# warship_demo_1.net
KiCad netlist of a schematic drawn in Altium Designer
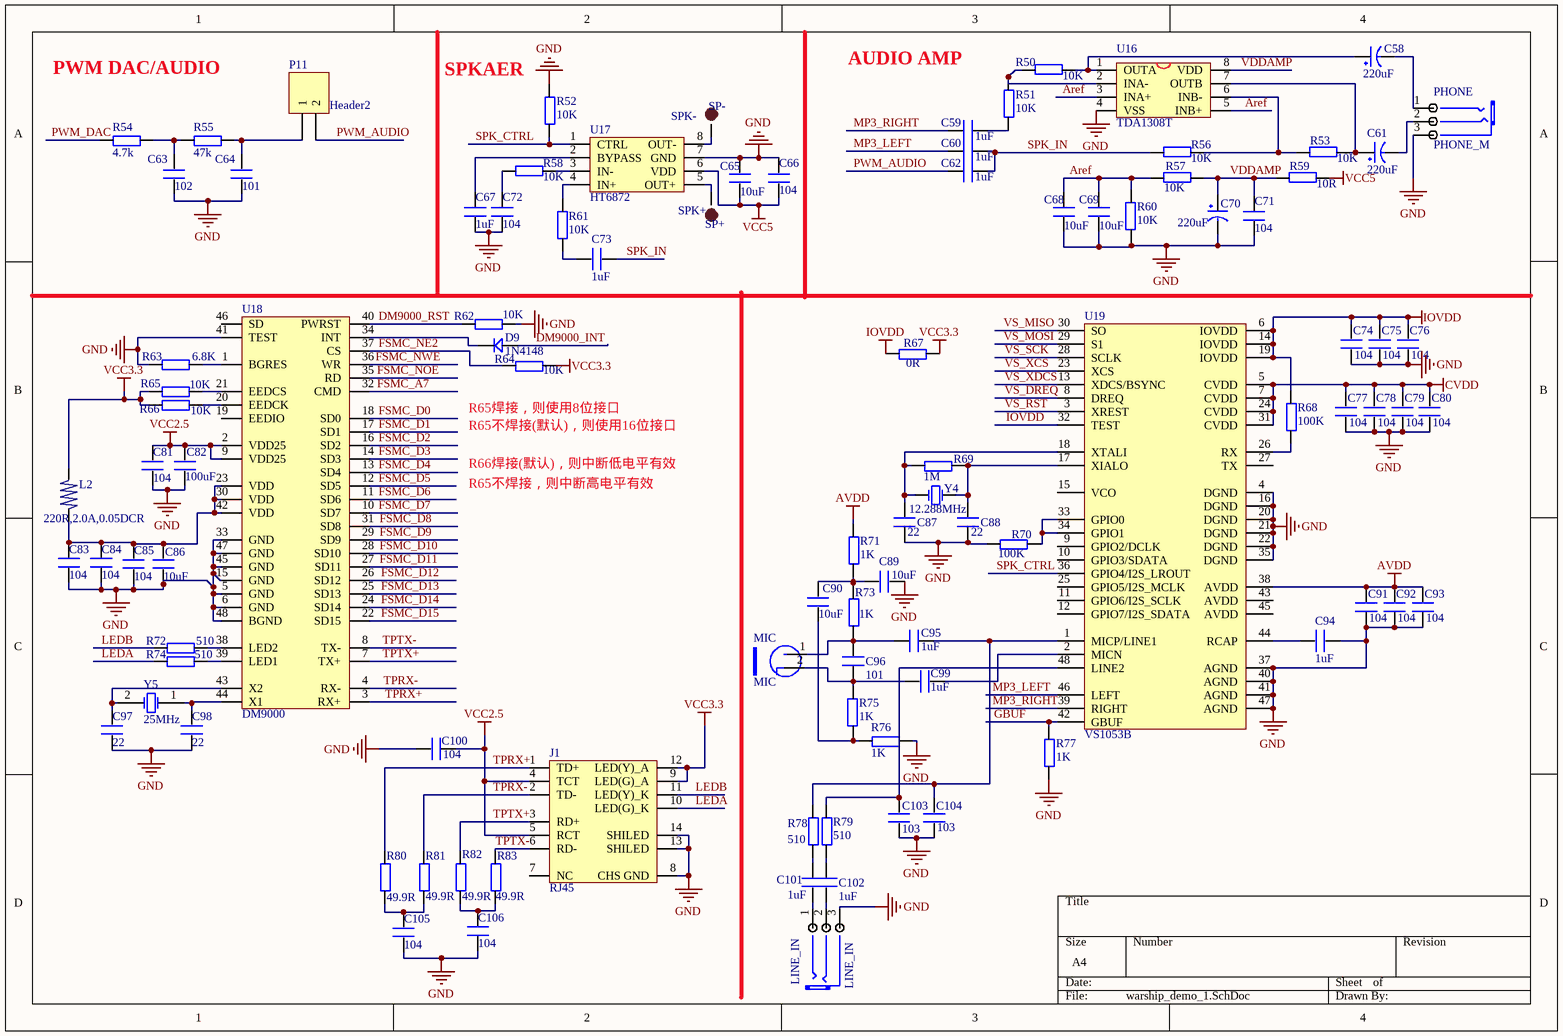
[diagram p0: warship_demo_1.SchDoc]

(export (version "E")
  (design (tool "Eeschema 10.0.6"))
  (components
    (comp (ref "C58") (value "220uF") (footprint "CC6.56.5") (libsource (lib "") (part "CAP_1")))
    (comp (ref "C59") (value "1uF") (footprint "0603P") (libsource (lib "WarShip V3 STM32103封装库") (part "C")))
    (comp (ref "C60") (value "1uF") (footprint "0603P") (libsource (lib "WarShip V3 STM32103封装库") (part "C")))
    (comp (ref "C61") (value "220uF") (footprint "CC6.56.5") (libsource (lib "") (part "CAP_1")))
    (comp (ref "C62") (value "1uF") (footprint "0603P") (libsource (lib "WarShip V3 STM32103封装库") (part "C")))
    (comp (ref "C63") (value "102") (footprint "0603P") (libsource (lib "WarShip V3 STM32103封装库") (part "C")))
    (comp (ref "C64") (value "101") (footprint "0603P") (libsource (lib "WarShip V3 STM32103封装库") (part "C")))
    (comp (ref "C65") (value "10uF") (footprint "0805") (libsource (lib "WarShip V3 STM32103封装库") (part "C")))
    (comp (ref "C66") (value "104") (footprint "0603P") (libsource (lib "WarShip V3 STM32103封装库") (part "C")))
    (comp (ref "C67") (value "1uF") (footprint "0603P") (libsource (lib "WarShip V3 STM32103封装库") (part "C")))
    (comp (ref "C68") (value "10uF") (footprint "0805") (libsource (lib "WarShip V3 STM32103封装库") (part "C")))
    (comp (ref "C69") (value "10uF") (footprint "0805") (libsource (lib "WarShip V3 STM32103封装库") (part "C")))
    (comp (ref "C70")
      (value "220uF")
      (footprint "CC6.56.5")
      (libsource (lib "WarShip V3 STM32103封装库") (part "CAP"))
    )
    (comp (ref "C71") (value "104") (footprint "0603P") (libsource (lib "WarShip V3 STM32103封装库") (part "C")))
    (comp (ref "C72") (value "104") (footprint "0603P") (libsource (lib "WarShip V3 STM32103封装库") (part "C")))
    (comp (ref "C73") (value "1uF") (footprint "0603P") (libsource (lib "WarShip V3 STM32103封装库") (part "C")))
    (comp (ref "C74") (value "104") (footprint "0603P") (libsource (lib "MP3模块封装库") (part "C")))
    (comp (ref "C75") (value "104") (footprint "0603P") (libsource (lib "MP3模块封装库") (part "C")))
    (comp (ref "C76") (value "104") (footprint "0603P") (libsource (lib "MP3模块封装库") (part "C")))
    (comp (ref "C77") (value "104") (footprint "0603P") (libsource (lib "MP3模块封装库") (part "C")))
    (comp (ref "C78") (value "104") (footprint "0603P") (libsource (lib "MP3模块封装库") (part "C")))
    (comp (ref "C79") (value "104") (footprint "0603P") (libsource (lib "MP3模块封装库") (part "C")))
    (comp (ref "C80") (value "104") (footprint "0603P") (libsource (lib "MP3模块封装库") (part "C")))
    (comp (ref "C81") (value "104") (footprint "0603P") (libsource (lib "WarShip V3 STM32103封装库") (part "C")))
    (comp (ref "C82")
      (value "100uF")
      (footprint "1206")
      (libsource (lib "WarShip V3 STM32103封装库") (part "C"))
    )
    (comp (ref "C83") (value "104") (footprint "0603P") (libsource (lib "WarShip V3 STM32103封装库") (part "C")))
    (comp (ref "C84") (value "104") (footprint "0603P") (libsource (lib "WarShip V3 STM32103封装库") (part "C")))
    (comp (ref "C85") (value "104") (footprint "0603P") (libsource (lib "WarShip V3 STM32103封装库") (part "C")))
    (comp (ref "C86") (value "10uF") (footprint "0805") (libsource (lib "WarShip V3 STM32103封装库") (part "C")))
    (comp (ref "C87") (value "22") (footprint "0603P") (libsource (lib "MP3模块封装库") (part "C")))
    (comp (ref "C88") (value "22") (footprint "0603P") (libsource (lib "MP3模块封装库") (part "C")))
    (comp (ref "C89") (value "10uF") (footprint "0805") (libsource (lib "WarShip V3 STM32103封装库") (part "C")))
    (comp (ref "C90") (value "10uF") (footprint "0805") (libsource (lib "WarShip V3 STM32103封装库") (part "C")))
    (comp (ref "C91") (value "104") (footprint "0603P") (libsource (lib "MP3模块封装库") (part "C")))
    (comp (ref "C92") (value "104") (footprint "0603P") (libsource (lib "MP3模块封装库") (part "C")))
    (comp (ref "C93") (value "104") (footprint "0603P") (libsource (lib "MP3模块封装库") (part "C")))
    (comp (ref "C94") (value "1uF") (footprint "0603P") (libsource (lib "MP3模块封装库") (part "C")))
    (comp (ref "C95") (value "1uF") (footprint "0603P") (libsource (lib "MP3模块封装库") (part "C")))
    (comp (ref "C96") (value "101") (footprint "0603P") (libsource (lib "MP3模块封装库") (part "C")))
    (comp (ref "C97") (value "22") (footprint "0603P") (libsource (lib "WarShip V3 STM32103封装库") (part "C")))
    (comp (ref "C98") (value "22") (footprint "0603P") (libsource (lib "WarShip V3 STM32103封装库") (part "C")))
    (comp (ref "C99") (value "1uF") (footprint "0603P") (libsource (lib "MP3模块封装库") (part "C")))
    (comp (ref "C100")
      (value "104")
      (footprint "0603P")
      (libsource (lib "WarShip V3 STM32103封装库") (part "C"))
    )
    (comp (ref "C101") (value "1uF") (footprint "0603P") (libsource (lib "MP3模块封装库") (part "C")))
    (comp (ref "C102") (value "1uF") (footprint "0603P") (libsource (lib "MP3模块封装库") (part "C")))
    (comp (ref "C103") (value "103") (footprint "0603P") (libsource (lib "MP3模块封装库") (part "C")))
    (comp (ref "C104") (value "103") (footprint "0603P") (libsource (lib "MP3模块封装库") (part "C")))
    (comp (ref "C105")
      (value "104")
      (footprint "0603P")
      (libsource (lib "WarShip V3 STM32103封装库") (part "C"))
    )
    (comp (ref "C106")
      (value "104")
      (footprint "0603P")
      (libsource (lib "WarShip V3 STM32103封装库") (part "C"))
    )
    (comp (ref "D9")
      (value "1N4148")
      (footprint "DIODE_SOP")
      (libsource (lib "WarShip V3 STM32103封装库") (part "D"))
    )
    (comp (ref "J1")
      (value "RJ45")
      (footprint "HR911105A")
      (libsource (lib "WarShip V3 STM32103封装库") (part "HR911105"))
    )
    (comp (ref "L2")
      (value "220R,2.0A,0.05DCR")
      (footprint "0603P")
      (libsource (lib "WarShip V3 STM32103封装库") (part "L"))
    )
    (comp (ref "LINE_IN")
      (value "LINE_IN")
      (footprint "PHONE_ST")
      (libsource (lib "MP3模块封装库") (part "PHONE_M"))
    )
    (comp (ref "MIC") (value "MIC") (footprint "MIC") (libsource (lib "MP3模块封装库") (part "MIC")))
    (comp (ref "P11")
      (value "Header2")
      (footprint "HDR1X2")
      (description "Header, 2-Pin")
      (fields (field (name "PUBLISHER") "Altium Limited"))
      (libsource (lib "WarShip V3 STM32103封装库") (part "Header 2"))
    )
    (comp (ref "PHONE")
      (value "PHONE_M")
      (footprint "PHONE_ST")
      (libsource (lib "WarShip V3 STM32103封装库") (part "PHONE_M"))
    )
    (comp (ref "R50") (value "10K") (footprint "0603P") (libsource (lib "WarShip V3 STM32103封装库") (part "R")))
    (comp (ref "R51") (value "10K") (footprint "0603P") (libsource (lib "WarShip V3 STM32103封装库") (part "R")))
    (comp (ref "R52") (value "10K") (footprint "0603P") (libsource (lib "WarShip V3 STM32103封装库") (part "R")))
    (comp (ref "R53") (value "10K") (footprint "0603P") (libsource (lib "WarShip V3 STM32103封装库") (part "R")))
    (comp (ref "R54")
      (value "4.7k")
      (footprint "0603P")
      (libsource (lib "WarShip V3 STM32103封装库") (part "R"))
    )
    (comp (ref "R55") (value "47k") (footprint "0603P") (libsource (lib "WarShip V3 STM32103封装库") (part "R")))
    (comp (ref "R56") (value "10K") (footprint "0603P") (libsource (lib "WarShip V3 STM32103封装库") (part "R")))
    (comp (ref "R57") (value "10K") (footprint "0603P") (libsource (lib "WarShip V3 STM32103封装库") (part "R")))
    (comp (ref "R58") (value "10K") (footprint "0603P") (libsource (lib "WarShip V3 STM32103封装库") (part "R")))
    (comp (ref "R59") (value "10R") (footprint "0603P") (libsource (lib "WarShip V3 STM32103封装库") (part "R")))
    (comp (ref "R60") (value "10K") (footprint "0603P") (libsource (lib "WarShip V3 STM32103封装库") (part "R")))
    (comp (ref "R61") (value "10K") (footprint "0603P") (libsource (lib "WarShip V3 STM32103封装库") (part "R")))
    (comp (ref "R62") (value "10K") (footprint "0603P") (libsource (lib "WarShip V3 STM32103封装库") (part "R")))
    (comp (ref "R63")
      (value "6.8K")
      (footprint "0603P")
      (libsource (lib "WarShip V3 STM32103封装库") (part "R"))
    )
    (comp (ref "R64") (value "10K") (footprint "0603P") (libsource (lib "WarShip V3 STM32103封装库") (part "R")))
    (comp (ref "R65") (value "10K") (footprint "0603P") (libsource (lib "WarShip V3 STM32103封装库") (part "R")))
    (comp (ref "R66") (value "10K") (footprint "0603P") (libsource (lib "WarShip V3 STM32103封装库") (part "R")))
    (comp (ref "R67") (value "0R") (footprint "0603P") (libsource (lib "MP3模块封装库") (part "R")))
    (comp (ref "R68") (value "100K") (footprint "0603P") (libsource (lib "MP3模块封装库") (part "R")))
    (comp (ref "R69") (value "1M") (footprint "0603P") (libsource (lib "MP3模块封装库") (part "R")))
    (comp (ref "R70") (value "100K") (footprint "0603P") (libsource (lib "MP3模块封装库") (part "R")))
    (comp (ref "R71") (value "1K") (footprint "0603P") (libsource (lib "MP3模块封装库") (part "R")))
    (comp (ref "R72") (value "510") (footprint "0603P") (libsource (lib "WarShip V3 STM32103封装库") (part "R")))
    (comp (ref "R73") (value "1K") (footprint "0603P") (libsource (lib "MP3模块封装库") (part "R")))
    (comp (ref "R74") (value "510") (footprint "0603P") (libsource (lib "WarShip V3 STM32103封装库") (part "R")))
    (comp (ref "R75") (value "1K") (footprint "0603P") (libsource (lib "MP3模块封装库") (part "R")))
    (comp (ref "R76") (value "1K") (footprint "0603P") (libsource (lib "MP3模块封装库") (part "R")))
    (comp (ref "R77") (value "1K") (footprint "0603P") (libsource (lib "MP3模块封装库") (part "R")))
    (comp (ref "R78") (value "510") (footprint "0603P") (libsource (lib "MP3模块封装库") (part "R")))
    (comp (ref "R79") (value "510") (footprint "0603P") (libsource (lib "MP3模块封装库") (part "R")))
    (comp (ref "R80")
      (value "49.9R")
      (footprint "0603P")
      (libsource (lib "WarShip V3 STM32103封装库") (part "R"))
    )
    (comp (ref "R81")
      (value "49.9R")
      (footprint "0603P")
      (libsource (lib "WarShip V3 STM32103封装库") (part "R"))
    )
    (comp (ref "R82")
      (value "49.9R")
      (footprint "0603P")
      (libsource (lib "WarShip V3 STM32103封装库") (part "R"))
    )
    (comp (ref "R83")
      (value "49.9R")
      (footprint "0603P")
      (libsource (lib "WarShip V3 STM32103封装库") (part "R"))
    )
    (comp (ref "SP+")
      (value "SPK+")
      (footprint "TP-1.5")
      (description "测试点")
      (libsource (lib "WarShip V3 STM32103封装库") (part "TEST-POINT"))
    )
    (comp (ref "SP-")
      (value "SPK-")
      (footprint "TP-1.5")
      (description "测试点")
      (libsource (lib "WarShip V3 STM32103封装库") (part "TEST-POINT"))
    )
    (comp (ref "U16")
      (value "TDA1308T")
      (footprint "SOP-8")
      (libsource (lib "WarShip V3 STM32103封装库") (part "TDA1308"))
    )
    (comp (ref "U17")
      (value "HT6872")
      (footprint "SOP-8")
      (description "HT6871")
      (libsource (lib "WarShip V3 STM32103封装库") (part "HT6871"))
    )
    (comp (ref "U18")
      (value "DM9000")
      (footprint "mTQFP48")
      (libsource (lib "WarShip V3 STM32103封装库") (part "DM9000A"))
    )
    (comp (ref "U19")
      (value "VS1053B")
      (footprint "mTQFP48")
      (libsource (lib "WarShip V3 STM32103封装库") (part "VS1053"))
    )
    (comp (ref "Y4")
      (value "12.288MHz")
      (footprint "XTAL_US")
      (description "Crystal Oscillator")
      (fields (field (name "PUBLISHER") "Altium Limited"))
      (libsource (lib "MP3模块封装库") (part "XTAL"))
    )
    (comp (ref "Y5")
      (value "25MHz")
      (footprint "XTAL_US")
      (description "Crystal Oscillator")
      (fields (field (name "PUBLISHER") "Altium Limited"))
      (libsource (lib "ENC28J60网络模块封装库") (part "XTAL"))
    )
  )
  (nets
    (net (code "1") (name "/Aref") (class "Default")
      (node (ref "C68") (pin "2") (pintype "passive"))
      (node (ref "C69") (pin "2") (pintype "passive"))
      (node (ref "R57") (pin "2") (pintype "passive"))
      (node (ref "R60") (pin "1") (pintype "passive"))
      (node (ref "U16") (pin "3") (pinfunction "INA+_3") (pintype "passive"))
      (node (ref "U16") (pin "5") (pinfunction "INB+_5") (pintype "passive"))
    )
    (net (code "2") (name "/DM9000_INT") (class "Default") (node (ref "D9") (pin "1") (pintype "passive")))
    (net (code "3") (name "/DM9000_RST") (class "Default")
      (node (ref "R62") (pin "1") (pintype "passive"))
      (node (ref "U18") (pin "40") (pinfunction "PWRST_40") (pintype "passive"))
    )
    (net (code "4") (name "/FSMC_A7") (class "Default")
      (node (ref "U18") (pin "32") (pinfunction "CMD_32") (pintype "passive"))
    )
    (net (code "5") (name "/FSMC_D0") (class "Default")
      (node (ref "U18") (pin "18") (pinfunction "SD0_18") (pintype "passive"))
    )
    (net (code "6") (name "/FSMC_D1") (class "Default")
      (node (ref "U18") (pin "17") (pinfunction "SD1_17") (pintype "passive"))
    )
    (net (code "7") (name "/FSMC_D2") (class "Default")
      (node (ref "U18") (pin "16") (pinfunction "SD2_16") (pintype "passive"))
    )
    (net (code "8") (name "/FSMC_D3") (class "Default")
      (node (ref "U18") (pin "14") (pinfunction "SD3_14") (pintype "passive"))
    )
    (net (code "9") (name "/FSMC_D4") (class "Default")
      (node (ref "U18") (pin "13") (pinfunction "SD4_13") (pintype "passive"))
    )
    (net (code "10") (name "/FSMC_D5") (class "Default")
      (node (ref "U18") (pin "12") (pinfunction "SD5_12") (pintype "passive"))
    )
    (net (code "11") (name "/FSMC_D6") (class "Default")
      (node (ref "U18") (pin "11") (pinfunction "SD6_11") (pintype "passive"))
    )
    (net (code "12") (name "/FSMC_D7") (class "Default")
      (node (ref "U18") (pin "10") (pinfunction "SD7_10") (pintype "passive"))
    )
    (net (code "13") (name "/FSMC_D8") (class "Default")
      (node (ref "U18") (pin "31") (pinfunction "SD8_31") (pintype "passive"))
    )
    (net (code "14") (name "/FSMC_D9") (class "Default")
      (node (ref "U18") (pin "29") (pinfunction "SD9_29") (pintype "passive"))
    )
    (net (code "15") (name "/FSMC_D10") (class "Default")
      (node (ref "U18") (pin "28") (pinfunction "SD10_28") (pintype "passive"))
    )
    (net (code "16") (name "/FSMC_D11") (class "Default")
      (node (ref "U18") (pin "27") (pinfunction "SD11_27") (pintype "passive"))
    )
    (net (code "17") (name "/FSMC_D12") (class "Default")
      (node (ref "U18") (pin "26") (pinfunction "SD12_26") (pintype "passive"))
    )
    (net (code "18") (name "/FSMC_D13") (class "Default")
      (node (ref "U18") (pin "25") (pinfunction "SD13_25") (pintype "passive"))
    )
    (net (code "19") (name "/FSMC_D14") (class "Default")
      (node (ref "U18") (pin "24") (pinfunction "SD14_24") (pintype "passive"))
    )
    (net (code "20") (name "/FSMC_D15") (class "Default")
      (node (ref "U18") (pin "22") (pinfunction "SD15_22") (pintype "passive"))
    )
    (net (code "21") (name "/FSMC_NE2") (class "Default")
      (node (ref "R64") (pin "1") (pintype "passive"))
      (node (ref "U18") (pin "37") (pinfunction "CS_37") (pintype "passive"))
    )
    (net (code "22") (name "/FSMC_NOE") (class "Default")
      (node (ref "U18") (pin "35") (pinfunction "RD_35") (pintype "passive"))
    )
    (net (code "23") (name "/FSMC_NWE") (class "Default")
      (node (ref "U18") (pin "36") (pinfunction "WR_36") (pintype "passive"))
    )
    (net (code "24") (name "/GBUF") (class "Default")
      (node (ref "R77") (pin "2") (pintype "passive"))
      (node (ref "U19") (pin "42") (pinfunction "GBUF_42") (pintype "passive"))
    )
    (net (code "25") (name "/LEDA") (class "Default")
      (node (ref "J1") (pin "10") (pinfunction "LED(G)_K_10") (pintype "passive"))
      (node (ref "R74") (pin "1") (pintype "passive"))
    )
    (net (code "26") (name "/LEDB") (class "Default")
      (node (ref "J1") (pin "11") (pinfunction "LED(Y)_K_11") (pintype "passive"))
      (node (ref "R72") (pin "1") (pintype "passive"))
    )
    (net (code "27") (name "/MP3_LEFT") (class "Default")
      (node (ref "C60") (pin "2") (pintype "passive"))
      (node (ref "U19") (pin "46") (pinfunction "LEFT_46") (pintype "passive"))
    )
    (net (code "28") (name "/MP3_RIGHT") (class "Default")
      (node (ref "C59") (pin "2") (pintype "passive"))
      (node (ref "U19") (pin "39") (pinfunction "RIGHT_39") (pintype "passive"))
    )
    (net (code "29") (name "/PWM_AUDIO") (class "Default")
      (node (ref "C62") (pin "2") (pintype "passive"))
      (node (ref "P11") (pin "2") (pinfunction "2_2") (pintype "passive"))
    )
    (net (code "30") (name "/PWM_DAC") (class "Default") (node (ref "R54") (pin "1") (pintype "passive")))
    (net (code "31") (name "/SPK_CTRL") (class "Default")
      (node (ref "R52") (pin "1") (pintype "passive"))
      (node (ref "U17") (pin "1") (pinfunction "CTRL_1") (pintype "passive"))
      (node (ref "U19") (pin "36") (pinfunction "GPIO4/I2S_LROUT_36") (pintype "passive"))
    )
    (net (code "32") (name "/SPK_IN") (class "Default")
      (node (ref "C60") (pin "1") (pintype "passive"))
      (node (ref "C62") (pin "1") (pintype "passive"))
      (node (ref "C73") (pin "1") (pintype "passive"))
      (node (ref "R56") (pin "2") (pintype "passive"))
    )
    (net (code "33") (name "/TPRX+") (class "Default")
      (node (ref "J1") (pin "1") (pinfunction "TD+_1") (pintype "passive"))
      (node (ref "R80") (pin "2") (pintype "passive"))
      (node (ref "U18") (pin "3") (pinfunction "RX+_3") (pintype "passive"))
    )
    (net (code "34") (name "/TPRX-") (class "Default")
      (node (ref "J1") (pin "2") (pinfunction "TD-_2") (pintype "passive"))
      (node (ref "R81") (pin "2") (pintype "passive"))
      (node (ref "U18") (pin "4") (pinfunction "RX-_4") (pintype "passive"))
    )
    (net (code "35") (name "/TPTX+") (class "Default")
      (node (ref "J1") (pin "3") (pinfunction "RD+_3") (pintype "passive"))
      (node (ref "R82") (pin "2") (pintype "passive"))
      (node (ref "U18") (pin "7") (pinfunction "TX+_7") (pintype "passive"))
    )
    (net (code "36") (name "/TPTX-") (class "Default")
      (node (ref "J1") (pin "6") (pinfunction "RD-_6") (pintype "passive"))
      (node (ref "R83") (pin "2") (pintype "passive"))
      (node (ref "U18") (pin "8") (pinfunction "TX-_8") (pintype "passive"))
    )
    (net (code "37") (name "/VDDAMP") (class "Default")
      (node (ref "C70") (pin "1") (pinfunction "VCC_1") (pintype "passive"))
      (node (ref "C71") (pin "1") (pintype "passive"))
      (node (ref "R57") (pin "1") (pintype "passive"))
      (node (ref "R59") (pin "2") (pintype "passive"))
      (node (ref "U16") (pin "8") (pinfunction "VDD_8") (pintype "passive"))
    )
    (net (code "38") (name "/VS_DREQ") (class "Default")
      (node (ref "U19") (pin "8") (pinfunction "DREQ_8") (pintype "passive"))
    )
    (net (code "39") (name "/VS_MISO") (class "Default")
      (node (ref "U19") (pin "30") (pinfunction "SO_30") (pintype "passive"))
    )
    (net (code "40") (name "/VS_MOSI") (class "Default")
      (node (ref "U19") (pin "29") (pinfunction "S1_29") (pintype "passive"))
    )
    (net (code "41") (name "/VS_RST") (class "Default")
      (node (ref "U19") (pin "3") (pinfunction "XREST_3") (pintype "passive"))
    )
    (net (code "42") (name "/VS_SCK") (class "Default")
      (node (ref "U19") (pin "28") (pinfunction "SCLK_28") (pintype "passive"))
    )
    (net (code "43") (name "/VS_XCS") (class "Default")
      (node (ref "U19") (pin "23") (pinfunction "XCS_23") (pintype "passive"))
    )
    (net (code "44") (name "/VS_XDCS") (class "Default")
      (node (ref "U19") (pin "13") (pinfunction "XDCS/BSYNC_13") (pintype "passive"))
    )
    (net (code "45") (name "AVDD") (class "Default")
      (node (ref "C91") (pin "2") (pintype "passive"))
      (node (ref "C92") (pin "2") (pintype "passive"))
      (node (ref "C93") (pin "2") (pintype "passive"))
      (node (ref "R71") (pin "2") (pintype "passive"))
      (node (ref "U19") (pin "38") (pinfunction "AVDD_38") (pintype "passive"))
    )
    (net (code "46") (name "CVDD") (class "Default")
      (node (ref "C77") (pin "2") (pintype "passive"))
      (node (ref "C78") (pin "2") (pintype "passive"))
      (node (ref "C79") (pin "2") (pintype "passive"))
      (node (ref "C80") (pin "2") (pintype "passive"))
      (node (ref "U19") (pin "24") (pinfunction "CVDD_24") (pintype "passive"))
      (node (ref "U19") (pin "31") (pinfunction "CVDD_31") (pintype "passive"))
      (node (ref "U19") (pin "5") (pinfunction "CVDD_5") (pintype "passive"))
      (node (ref "U19") (pin "7") (pinfunction "CVDD_7") (pintype "passive"))
    )
    (net (code "47") (name "GND") (class "Default")
      (node (ref "C100") (pin "2") (pintype "passive"))
      (node (ref "C103") (pin "1") (pintype "passive"))
      (node (ref "C104") (pin "1") (pintype "passive"))
      (node (ref "C105") (pin "1") (pintype "passive"))
      (node (ref "C106") (pin "1") (pintype "passive"))
      (node (ref "C63") (pin "1") (pintype "passive"))
      (node (ref "C64") (pin "1") (pintype "passive"))
      (node (ref "C65") (pin "2") (pintype "passive"))
      (node (ref "C66") (pin "1") (pintype "passive"))
      (node (ref "C67") (pin "1") (pintype "passive"))
      (node (ref "C68") (pin "1") (pintype "passive"))
      (node (ref "C69") (pin "1") (pintype "passive"))
      (node (ref "C70") (pin "2") (pinfunction "GND_2") (pintype "passive"))
      (node (ref "C71") (pin "2") (pintype "passive"))
      (node (ref "C72") (pin "1") (pintype "passive"))
      (node (ref "C74") (pin "1") (pintype "passive"))
      (node (ref "C75") (pin "1") (pintype "passive"))
      (node (ref "C76") (pin "1") (pintype "passive"))
      (node (ref "C77") (pin "1") (pintype "passive"))
      (node (ref "C78") (pin "1") (pintype "passive"))
      (node (ref "C79") (pin "1") (pintype "passive"))
      (node (ref "C80") (pin "1") (pintype "passive"))
      (node (ref "C81") (pin "1") (pintype "passive"))
      (node (ref "C82") (pin "1") (pintype "passive"))
      (node (ref "C83") (pin "1") (pintype "passive"))
      (node (ref "C84") (pin "1") (pintype "passive"))
      (node (ref "C85") (pin "1") (pintype "passive"))
      (node (ref "C86") (pin "1") (pintype "passive"))
      (node (ref "C87") (pin "1") (pintype "passive"))
      (node (ref "C88") (pin "2") (pintype "passive"))
      (node (ref "C89") (pin "1") (pintype "passive"))
      (node (ref "C91") (pin "1") (pintype "passive"))
      (node (ref "C92") (pin "1") (pintype "passive"))
      (node (ref "C93") (pin "1") (pintype "passive"))
      (node (ref "C94") (pin "1") (pintype "passive"))
      (node (ref "C97") (pin "1") (pintype "passive"))
      (node (ref "C98") (pin "1") (pintype "passive"))
      (node (ref "J1") (pin "13") (pinfunction "SHILED_13") (pintype "passive"))
      (node (ref "J1") (pin "14") (pinfunction "SHILED_14") (pintype "passive"))
      (node (ref "J1") (pin "8") (pinfunction "CHS_GND_8") (pintype "passive"))
      (node (ref "LINE_IN") (pin "3") (pinfunction "COM_3") (pintype "passive"))
      (node (ref "PHONE") (pin "3") (pinfunction "COM_3") (pintype "passive"))
      (node (ref "R52") (pin "2") (pintype "passive"))
      (node (ref "R60") (pin "2") (pintype "passive"))
      (node (ref "R62") (pin "2") (pintype "passive"))
      (node (ref "R63") (pin "1") (pintype "passive"))
      (node (ref "R70") (pin "1") (pintype "passive"))
      (node (ref "R76") (pin "2") (pintype "passive"))
      (node (ref "R77") (pin "1") (pintype "passive"))
      (node (ref "U16") (pin "4") (pinfunction "VSS_4") (pintype "passive"))
      (node (ref "U17") (pin "7") (pinfunction "GND_7") (pintype "passive"))
      (node (ref "U18") (pin "15") (pinfunction "GND_15") (pintype "passive"))
      (node (ref "U18") (pin "33") (pinfunction "GND_33") (pintype "passive"))
      (node (ref "U18") (pin "41") (pinfunction "TEST_41") (pintype "passive"))
      (node (ref "U18") (pin "45") (pinfunction "GND_45") (pintype "passive"))
      (node (ref "U18") (pin "47") (pinfunction "GND_47") (pintype "passive"))
      (node (ref "U18") (pin "48") (pinfunction "BGND_48") (pintype "passive"))
      (node (ref "U18") (pin "5") (pinfunction "GND_5") (pintype "passive"))
      (node (ref "U18") (pin "6") (pinfunction "GND_6") (pintype "passive"))
      (node (ref "U19") (pin "16") (pinfunction "DGND_16") (pintype "passive"))
      (node (ref "U19") (pin "20") (pinfunction "DGND_20") (pintype "passive"))
      (node (ref "U19") (pin "21") (pinfunction "DGND_21") (pintype "passive"))
      (node (ref "U19") (pin "22") (pinfunction "DGND_22") (pintype "passive"))
      (node (ref "U19") (pin "35") (pinfunction "DGND_35") (pintype "passive"))
      (node (ref "U19") (pin "37") (pinfunction "AGND_37") (pintype "passive"))
      (node (ref "U19") (pin "4") (pinfunction "DGND_4") (pintype "passive"))
      (node (ref "U19") (pin "40") (pinfunction "AGND_40") (pintype "passive"))
      (node (ref "U19") (pin "41") (pinfunction "AGND_41") (pintype "passive"))
      (node (ref "U19") (pin "47") (pinfunction "AGND_47") (pintype "passive"))
    )
    (net (code "48") (name "IOVDD") (class "Default")
      (node (ref "C74") (pin "2") (pintype "passive"))
      (node (ref "C75") (pin "2") (pintype "passive"))
      (node (ref "C76") (pin "2") (pintype "passive"))
      (node (ref "R67") (pin "1") (pintype "passive"))
      (node (ref "R68") (pin "2") (pintype "passive"))
      (node (ref "U19") (pin "14") (pinfunction "IOVDD_14") (pintype "passive"))
      (node (ref "U19") (pin "19") (pinfunction "IOVDD_19") (pintype "passive"))
      (node (ref "U19") (pin "32") (pinfunction "TEST_32") (pintype "passive"))
      (node (ref "U19") (pin "6") (pinfunction "IOVDD_6") (pintype "passive"))
    )
    (net (code "49") (name "Net-(C58-GND)") (class "Default")
      (node (ref "C58") (pin "2") (pinfunction "GND_2") (pintype "passive"))
      (node (ref "PHONE") (pin "1") (pinfunction "CHL_1") (pintype "passive"))
    )
    (net (code "50") (name "Net-(C58-VCC)") (class "Default")
      (node (ref "C58") (pin "1") (pinfunction "VCC_1") (pintype "passive"))
      (node (ref "R50") (pin "1") (pintype "passive"))
      (node (ref "U16") (pin "1") (pinfunction "OUTA_1") (pintype "passive"))
    )
    (net (code "51") (name "Net-(C59-Pad1)") (class "Default")
      (node (ref "C59") (pin "1") (pintype "passive"))
      (node (ref "R51") (pin "1") (pintype "passive"))
    )
    (net (code "52") (name "Net-(C61-GND)") (class "Default")
      (node (ref "C61") (pin "2") (pinfunction "GND_2") (pintype "passive"))
      (node (ref "PHONE") (pin "2") (pinfunction "CHR_2") (pintype "passive"))
    )
    (net (code "53") (name "Net-(C61-VCC)") (class "Default")
      (node (ref "C61") (pin "1") (pinfunction "VCC_1") (pintype "passive"))
      (node (ref "R53") (pin "1") (pintype "passive"))
      (node (ref "U16") (pin "7") (pinfunction "OUTB_7") (pintype "passive"))
    )
    (net (code "54") (name "Net-(C63-Pad2)") (class "Default")
      (node (ref "C63") (pin "2") (pintype "passive"))
      (node (ref "R54") (pin "2") (pintype "passive"))
      (node (ref "R55") (pin "1") (pintype "passive"))
    )
    (net (code "55") (name "Net-(C64-Pad2)") (class "Default")
      (node (ref "C64") (pin "2") (pintype "passive"))
      (node (ref "P11") (pin "1") (pinfunction "1_1") (pintype "passive"))
      (node (ref "R55") (pin "2") (pintype "passive"))
    )
    (net (code "56") (name "Net-(C72-Pad2)") (class "Default")
      (node (ref "C72") (pin "2") (pintype "passive"))
      (node (ref "R58") (pin "2") (pintype "passive"))
    )
    (net (code "57") (name "Net-(C73-Pad2)") (class "Default")
      (node (ref "C73") (pin "2") (pintype "passive"))
      (node (ref "R61") (pin "2") (pintype "passive"))
    )
    (net (code "58") (name "Net-(C83-Pad2)") (class "Default")
      (node (ref "C83") (pin "2") (pintype "passive"))
      (node (ref "C84") (pin "2") (pintype "passive"))
      (node (ref "C85") (pin "2") (pintype "passive"))
      (node (ref "C86") (pin "2") (pintype "passive"))
      (node (ref "L2") (pin "2") (pintype "passive"))
      (node (ref "U18") (pin "23") (pinfunction "VDD_23") (pintype "passive"))
      (node (ref "U18") (pin "30") (pinfunction "VDD_30") (pintype "passive"))
      (node (ref "U18") (pin "42") (pinfunction "VDD_42") (pintype "passive"))
    )
    (net (code "59") (name "Net-(C89-Pad2)") (class "Default")
      (node (ref "C89") (pin "2") (pintype "passive"))
      (node (ref "C90") (pin "2") (pintype "passive"))
      (node (ref "R71") (pin "1") (pintype "passive"))
      (node (ref "R73") (pin "2") (pintype "passive"))
    )
    (net (code "60") (name "Net-(C90-Pad1)") (class "Default")
      (node (ref "C90") (pin "1") (pintype "passive"))
      (node (ref "R75") (pin "2") (pintype "passive"))
      (node (ref "R76") (pin "1") (pintype "passive"))
    )
    (net (code "61") (name "Net-(C101-Pad2)") (class "Default")
      (node (ref "C101") (pin "2") (pintype "passive"))
      (node (ref "R78") (pin "1") (pintype "passive"))
    )
    (net (code "62") (name "Net-(C102-Pad2)") (class "Default")
      (node (ref "C102") (pin "2") (pintype "passive"))
      (node (ref "R79") (pin "1") (pintype "passive"))
    )
    (net (code "63") (name "Net-(C105-Pad2)") (class "Default")
      (node (ref "C105") (pin "2") (pintype "passive"))
      (node (ref "R80") (pin "1") (pintype "passive"))
      (node (ref "R81") (pin "1") (pintype "passive"))
    )
    (net (code "64") (name "Net-(C106-Pad2)") (class "Default")
      (node (ref "C106") (pin "2") (pintype "passive"))
      (node (ref "R82") (pin "1") (pintype "passive"))
      (node (ref "R83") (pin "1") (pintype "passive"))
    )
    (net (code "65") (name "Net-(LINE_IN-CHL)") (class "Default")
      (node (ref "C101") (pin "1") (pintype "passive"))
      (node (ref "LINE_IN") (pin "1") (pinfunction "CHL_1") (pintype "passive"))
    )
    (net (code "66") (name "Net-(LINE_IN-CHR)") (class "Default")
      (node (ref "C102") (pin "1") (pintype "passive"))
      (node (ref "LINE_IN") (pin "2") (pinfunction "CHR_2") (pintype "passive"))
    )
    (net (code "67") (name "Net-(MIC-GND)") (class "Default")
      (node (ref "C96") (pin "1") (pintype "passive"))
      (node (ref "C99") (pin "1") (pintype "passive"))
      (node (ref "MIC") (pin "2") (pinfunction "GND_2") (pintype "passive"))
      (node (ref "R75") (pin "1") (pintype "passive"))
    )
    (net (code "68") (name "Net-(MIC-VCC)") (class "Default")
      (node (ref "C95") (pin "1") (pintype "passive"))
      (node (ref "C96") (pin "2") (pintype "passive"))
      (node (ref "MIC") (pin "1") (pinfunction "VCC_1") (pintype "passive"))
      (node (ref "R73") (pin "1") (pintype "passive"))
    )
    (net (code "69") (name "Net-(U16-INA-)") (class "Default")
      (node (ref "R50") (pin "2") (pintype "passive"))
      (node (ref "R51") (pin "2") (pintype "passive"))
      (node (ref "U16") (pin "2") (pinfunction "INA-_2") (pintype "passive"))
    )
    (net (code "70") (name "Net-(U16-INB-)") (class "Default")
      (node (ref "R53") (pin "2") (pintype "passive"))
      (node (ref "R56") (pin "1") (pintype "passive"))
      (node (ref "U16") (pin "6") (pinfunction "INB-_6") (pintype "passive"))
    )
    (net (code "71") (name "Net-(U17-BYPASS)") (class "Default")
      (node (ref "C67") (pin "2") (pintype "passive"))
      (node (ref "U17") (pin "2") (pinfunction "BYPASS_2") (pintype "passive"))
    )
    (net (code "72") (name "Net-(U17-IN+)") (class "Default")
      (node (ref "R61") (pin "1") (pintype "passive"))
      (node (ref "U17") (pin "4") (pinfunction "IN+_4") (pintype "passive"))
    )
    (net (code "73") (name "Net-(U17-IN-)") (class "Default")
      (node (ref "R58") (pin "1") (pintype "passive"))
      (node (ref "U17") (pin "3") (pinfunction "IN-_3") (pintype "passive"))
    )
    (net (code "74") (name "Net-(U17-OUT+)") (class "Default")
      (node (ref "SP+") (pin "1") (pinfunction "1_1") (pintype "passive"))
      (node (ref "U17") (pin "5") (pinfunction "OUT+_5") (pintype "passive"))
    )
    (net (code "75") (name "Net-(U17-OUT-)") (class "Default")
      (node (ref "SP-") (pin "1") (pinfunction "1_1") (pintype "passive"))
      (node (ref "U17") (pin "8") (pinfunction "OUT-_8") (pintype "passive"))
    )
    (net (code "76") (name "Net-(U18-BGRES)") (class "Default")
      (node (ref "R63") (pin "2") (pintype "passive"))
      (node (ref "U18") (pin "1") (pinfunction "BGRES_1") (pintype "passive"))
    )
    (net (code "77") (name "Net-(U18-EEDCK)") (class "Default")
      (node (ref "R66") (pin "2") (pintype "passive"))
      (node (ref "U18") (pin "20") (pinfunction "EEDCK_20") (pintype "passive"))
    )
    (net (code "78") (name "Net-(U18-EEDCS)") (class "Default")
      (node (ref "R65") (pin "2") (pintype "passive"))
      (node (ref "U18") (pin "21") (pinfunction "EEDCS_21") (pintype "passive"))
    )
    (net (code "79") (name "Net-(U18-INT)") (class "Default")
      (node (ref "D9") (pin "2") (pintype "passive"))
      (node (ref "U18") (pin "34") (pinfunction "INT_34") (pintype "passive"))
    )
    (net (code "80") (name "Net-(U18-LED1)") (class "Default")
      (node (ref "R74") (pin "2") (pintype "passive"))
      (node (ref "U18") (pin "39") (pinfunction "LED1_39") (pintype "passive"))
    )
    (net (code "81") (name "Net-(U18-LED2)") (class "Default")
      (node (ref "R72") (pin "2") (pintype "passive"))
      (node (ref "U18") (pin "38") (pinfunction "LED2_38") (pintype "passive"))
    )
    (net (code "82") (name "Net-(U18-X1)") (class "Default")
      (node (ref "C98") (pin "2") (pintype "passive"))
      (node (ref "U18") (pin "44") (pinfunction "X1_44") (pintype "passive"))
      (node (ref "Y5") (pin "1") (pinfunction "OSC1_1") (pintype "passive"))
    )
    (net (code "83") (name "Net-(U18-X2)") (class "Default")
      (node (ref "C97") (pin "2") (pintype "passive"))
      (node (ref "U18") (pin "43") (pinfunction "X2_43") (pintype "passive"))
      (node (ref "Y5") (pin "2") (pinfunction "OSC2_2") (pintype "passive"))
    )
    (net (code "84") (name "Net-(U19-GPIO0)") (class "Default")
      (node (ref "R70") (pin "2") (pintype "passive"))
      (node (ref "U19") (pin "33") (pinfunction "GPIO0_33") (pintype "passive"))
      (node (ref "U19") (pin "34") (pinfunction "GPIO1_34") (pintype "passive"))
    )
    (net (code "85") (name "Net-(U19-LINE2)") (class "Default")
      (node (ref "C103") (pin "2") (pintype "passive"))
      (node (ref "R79") (pin "2") (pintype "passive"))
      (node (ref "U19") (pin "48") (pinfunction "LINE2_48") (pintype "passive"))
    )
    (net (code "86") (name "Net-(U19-MICN)") (class "Default")
      (node (ref "C99") (pin "2") (pintype "passive"))
      (node (ref "U19") (pin "2") (pinfunction "MICN_2") (pintype "passive"))
    )
    (net (code "87") (name "Net-(U19-MICP{slash}LINE1)") (class "Default")
      (node (ref "C104") (pin "2") (pintype "passive"))
      (node (ref "C95") (pin "2") (pintype "passive"))
      (node (ref "R78") (pin "2") (pintype "passive"))
      (node (ref "U19") (pin "1") (pinfunction "MICP/LINE1_1") (pintype "passive"))
    )
    (net (code "88") (name "Net-(U19-RCAP)") (class "Default")
      (node (ref "C94") (pin "2") (pintype "passive"))
      (node (ref "U19") (pin "44") (pinfunction "RCAP_44") (pintype "passive"))
    )
    (net (code "89") (name "Net-(U19-RX)") (class "Default")
      (node (ref "R68") (pin "1") (pintype "passive"))
      (node (ref "U19") (pin "26") (pinfunction "RX_26") (pintype "passive"))
    )
    (net (code "90") (name "Net-(U19-XIALO)") (class "Default")
      (node (ref "C88") (pin "1") (pintype "passive"))
      (node (ref "R69") (pin "2") (pintype "passive"))
      (node (ref "U19") (pin "17") (pinfunction "XIALO_17") (pintype "passive"))
      (node (ref "Y4") (pin "2") (pinfunction "OSC2_2") (pintype "passive"))
    )
    (net (code "91") (name "Net-(U19-XTALI)") (class "Default")
      (node (ref "C87") (pin "2") (pintype "passive"))
      (node (ref "R69") (pin "1") (pintype "passive"))
      (node (ref "U19") (pin "18") (pinfunction "XTALI_18") (pintype "passive"))
      (node (ref "Y4") (pin "1") (pinfunction "OSC1_1") (pintype "passive"))
    )
    (net (code "92") (name "VCC2.5") (class "Default")
      (node (ref "C100") (pin "1") (pintype "passive"))
      (node (ref "C81") (pin "2") (pintype "passive"))
      (node (ref "C82") (pin "2") (pintype "passive"))
      (node (ref "J1") (pin "4") (pinfunction "TCT_4") (pintype "passive"))
      (node (ref "J1") (pin "5") (pinfunction "RCT_5") (pintype "passive"))
      (node (ref "U18") (pin "2") (pinfunction "VDD25_2") (pintype "passive"))
      (node (ref "U18") (pin "9") (pinfunction "VDD25_9") (pintype "passive"))
    )
    (net (code "93") (name "VCC3.3") (class "Default")
      (node (ref "J1") (pin "12") (pinfunction "LED(Y)_A_12") (pintype "passive"))
      (node (ref "J1") (pin "9") (pinfunction "LED(G)_A_9") (pintype "passive"))
      (node (ref "L2") (pin "1") (pintype "passive"))
      (node (ref "R64") (pin "2") (pintype "passive"))
      (node (ref "R65") (pin "1") (pintype "passive"))
      (node (ref "R66") (pin "1") (pintype "passive"))
      (node (ref "R67") (pin "2") (pintype "passive"))
    )
    (net (code "94") (name "VCC5") (class "Default")
      (node (ref "C65") (pin "1") (pintype "passive"))
      (node (ref "C66") (pin "2") (pintype "passive"))
      (node (ref "R59") (pin "1") (pintype "passive"))
      (node (ref "U17") (pin "6") (pinfunction "VDD_6") (pintype "passive"))
    )
    (net (code "95") (name "unconnected-(J1-NC-Pad7)") (class "Default")
      (node (ref "J1") (pin "7") (pinfunction "NC_7") (pintype "passive"))
    )
    (net (code "96") (name "unconnected-(U18-EEDIO-Pad19)") (class "Default")
      (node (ref "U18") (pin "19") (pinfunction "EEDIO_19") (pintype "passive"))
    )
    (net (code "97") (name "unconnected-(U18-SD-Pad46)") (class "Default")
      (node (ref "U18") (pin "46") (pinfunction "SD_46") (pintype "passive"))
    )
    (net (code "98") (name "unconnected-(U19-AVDD-Pad43)") (class "Default")
      (node (ref "U19") (pin "43") (pinfunction "AVDD_43") (pintype "passive"))
    )
    (net (code "99") (name "unconnected-(U19-AVDD-Pad45)") (class "Default")
      (node (ref "U19") (pin "45") (pinfunction "AVDD_45") (pintype "passive"))
    )
    (net (code "100") (name "unconnected-(U19-GPIO2{slash}DCLK-Pad9)") (class "Default")
      (node (ref "U19") (pin "9") (pinfunction "GPIO2/DCLK_9") (pintype "passive"))
    )
    (net (code "101") (name "unconnected-(U19-GPIO3{slash}SDATA-Pad10)") (class "Default")
      (node (ref "U19") (pin "10") (pinfunction "GPIO3/SDATA_10") (pintype "passive"))
    )
    (net (code "102") (name "unconnected-(U19-GPIO5{slash}I2S_MCLK-Pad25)") (class "Default")
      (node (ref "U19") (pin "25") (pinfunction "GPIO5/I2S_MCLK_25") (pintype "passive"))
    )
    (net (code "103") (name "unconnected-(U19-GPIO6{slash}I2S_SCLK-Pad11)") (class "Default")
      (node (ref "U19") (pin "11") (pinfunction "GPIO6/I2S_SCLK_11") (pintype "passive"))
    )
    (net (code "104") (name "unconnected-(U19-GPIO7{slash}I2S_SDATA-Pad12)") (class "Default")
      (node (ref "U19") (pin "12") (pinfunction "GPIO7/I2S_SDATA_12") (pintype "passive"))
    )
    (net (code "105") (name "unconnected-(U19-TX-Pad27)") (class "Default")
      (node (ref "U19") (pin "27") (pinfunction "TX_27") (pintype "passive"))
    )
    (net (code "106") (name "unconnected-(U19-VCO-Pad15)") (class "Default")
      (node (ref "U19") (pin "15") (pinfunction "VCO_15") (pintype "passive"))
    )
  )
)
